# rev_b.net
KiCad netlist of a schematic drawn in EAGLE
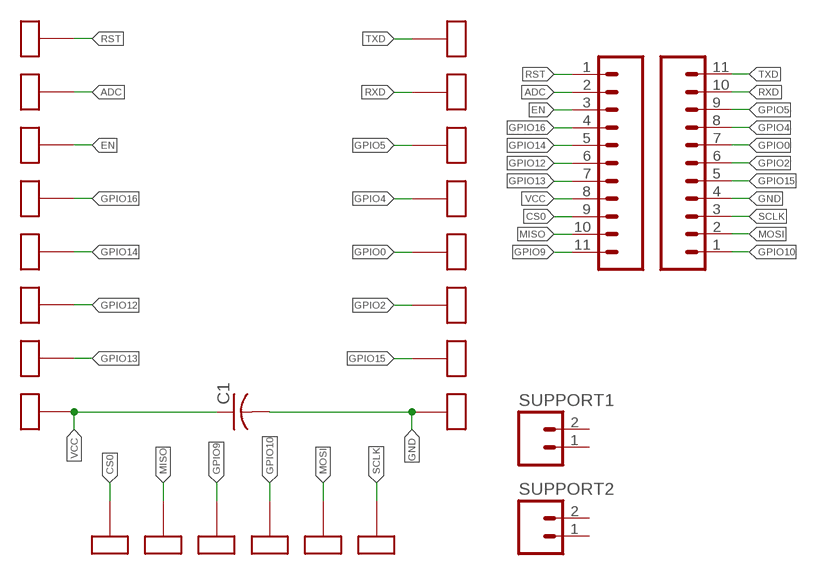
[diagram p0: schematic, sheet 1]

(export (version "E")
  (design (tool "Eeschema 10.0.6"))
  (components
    (comp (ref "C1")
      (value "C-USC0805")
      (footprint "eagle-import:C0805")
      (libsource (lib "eagle-import") (part "C-USC0805"))
    )
    (comp (ref "JP1")
      (value "M11LOCK")
      (footprint "eagle-import:1X11_LOCK")
      (libsource (lib "eagle-import") (part "M11LOCK"))
    )
    (comp (ref "JP2")
      (value "M11LOCK")
      (footprint "eagle-import:1X11_LOCK")
      (libsource (lib "eagle-import") (part "M11LOCK"))
    )
    (comp (ref "SUPPORT1")
      (value "M02LOCK")
      (footprint "eagle-import:1X02_LOCK")
      (libsource (lib "eagle-import") (part "M02LOCK"))
    )
    (comp (ref "SUPPORT2")
      (value "M02LOCK")
      (footprint "eagle-import:1X02_LOCK")
      (libsource (lib "eagle-import") (part "M02LOCK"))
    )
    (comp (ref "U$2")
      (value "1MMPOGO")
      (footprint "eagle-import:1MMPOGO")
      (libsource (lib "eagle-import") (part "1MMPOGO"))
    )
    (comp (ref "U$3")
      (value "1MMPOGO")
      (footprint "eagle-import:1MMPOGO")
      (libsource (lib "eagle-import") (part "1MMPOGO"))
    )
    (comp (ref "U$4")
      (value "1MMPOGO")
      (footprint "eagle-import:1MMPOGO")
      (libsource (lib "eagle-import") (part "1MMPOGO"))
    )
    (comp (ref "U$5")
      (value "1MMPOGO")
      (footprint "eagle-import:1MMPOGO")
      (libsource (lib "eagle-import") (part "1MMPOGO"))
    )
    (comp (ref "U$6")
      (value "1MMPOGO")
      (footprint "eagle-import:1MMPOGO")
      (libsource (lib "eagle-import") (part "1MMPOGO"))
    )
    (comp (ref "U$7")
      (value "1MMPOGO")
      (footprint "eagle-import:1MMPOGO")
      (libsource (lib "eagle-import") (part "1MMPOGO"))
    )
    (comp (ref "U$8")
      (value "1MMPOGO")
      (footprint "eagle-import:1MMPOGO")
      (libsource (lib "eagle-import") (part "1MMPOGO"))
    )
    (comp (ref "U$9")
      (value "1MMPOGO")
      (footprint "eagle-import:1MMPOGO")
      (libsource (lib "eagle-import") (part "1MMPOGO"))
    )
    (comp (ref "U$10")
      (value "1MMPOGO")
      (footprint "eagle-import:1MMPOGO")
      (libsource (lib "eagle-import") (part "1MMPOGO"))
    )
    (comp (ref "U$11")
      (value "1MMPOGO")
      (footprint "eagle-import:1MMPOGO")
      (libsource (lib "eagle-import") (part "1MMPOGO"))
    )
    (comp (ref "U$12")
      (value "1MMPOGO")
      (footprint "eagle-import:1MMPOGO")
      (libsource (lib "eagle-import") (part "1MMPOGO"))
    )
    (comp (ref "U$13")
      (value "1MMPOGO")
      (footprint "eagle-import:1MMPOGO")
      (libsource (lib "eagle-import") (part "1MMPOGO"))
    )
    (comp (ref "U$14")
      (value "1MMPOGO")
      (footprint "eagle-import:1MMPOGO")
      (libsource (lib "eagle-import") (part "1MMPOGO"))
    )
    (comp (ref "U$15")
      (value "1MMPOGO")
      (footprint "eagle-import:1MMPOGO")
      (libsource (lib "eagle-import") (part "1MMPOGO"))
    )
    (comp (ref "U$16")
      (value "1MMPOGO")
      (footprint "eagle-import:1MMPOGO")
      (libsource (lib "eagle-import") (part "1MMPOGO"))
    )
    (comp (ref "U$17")
      (value "1MMPOGO")
      (footprint "eagle-import:1MMPOGO")
      (libsource (lib "eagle-import") (part "1MMPOGO"))
    )
    (comp (ref "U$18")
      (value "1MMPOGO")
      (footprint "eagle-import:1MMPOGO")
      (libsource (lib "eagle-import") (part "1MMPOGO"))
    )
    (comp (ref "U$19")
      (value "1MMPOGO")
      (footprint "eagle-import:1MMPOGO")
      (libsource (lib "eagle-import") (part "1MMPOGO"))
    )
    (comp (ref "U$20")
      (value "1MMPOGO")
      (footprint "eagle-import:1MMPOGO")
      (libsource (lib "eagle-import") (part "1MMPOGO"))
    )
    (comp (ref "U$21")
      (value "1MMPOGO")
      (footprint "eagle-import:1MMPOGO")
      (libsource (lib "eagle-import") (part "1MMPOGO"))
    )
    (comp (ref "U$22")
      (value "1MMPOGO")
      (footprint "eagle-import:1MMPOGO")
      (libsource (lib "eagle-import") (part "1MMPOGO"))
    )
    (comp (ref "U$23")
      (value "1MMPOGO")
      (footprint "eagle-import:1MMPOGO")
      (libsource (lib "eagle-import") (part "1MMPOGO"))
    )
  )
  (nets
    (net (code "1") (name "ADC") (class "Default")
      (node (ref "JP1") (pin "2") (pinfunction "2_2") (pintype "passive"))
      (node (ref "U$3") (pin "POGO") (pinfunction "P_POGO") (pintype "bidirectional"))
    )
    (net (code "2") (name "CS0") (class "Default")
      (node (ref "JP1") (pin "9") (pinfunction "9_9") (pintype "passive"))
      (node (ref "U$10") (pin "POGO") (pinfunction "P_POGO") (pintype "bidirectional"))
    )
    (net (code "3") (name "EN") (class "Default")
      (node (ref "JP1") (pin "3") (pinfunction "3_3") (pintype "passive"))
      (node (ref "U$4") (pin "POGO") (pinfunction "P_POGO") (pintype "bidirectional"))
    )
    (net (code "4") (name "GND") (class "Default")
      (node (ref "C1") (pin "2") (pinfunction "2_2") (pintype "passive"))
      (node (ref "JP2") (pin "4") (pinfunction "4_4") (pintype "passive"))
      (node (ref "U$16") (pin "POGO") (pinfunction "P_POGO") (pintype "bidirectional"))
    )
    (net (code "5") (name "GPIO0") (class "Default")
      (node (ref "JP2") (pin "7") (pinfunction "7_7") (pintype "passive"))
      (node (ref "U$19") (pin "POGO") (pinfunction "P_POGO") (pintype "bidirectional"))
    )
    (net (code "6") (name "GPIO2") (class "Default")
      (node (ref "JP2") (pin "6") (pinfunction "6_6") (pintype "passive"))
      (node (ref "U$18") (pin "POGO") (pinfunction "P_POGO") (pintype "bidirectional"))
    )
    (net (code "7") (name "GPIO4") (class "Default")
      (node (ref "JP2") (pin "8") (pinfunction "8_8") (pintype "passive"))
      (node (ref "U$20") (pin "POGO") (pinfunction "P_POGO") (pintype "bidirectional"))
    )
    (net (code "8") (name "GPIO5") (class "Default")
      (node (ref "JP2") (pin "9") (pinfunction "9_9") (pintype "passive"))
      (node (ref "U$21") (pin "POGO") (pinfunction "P_POGO") (pintype "bidirectional"))
    )
    (net (code "9") (name "GPIO9") (class "Default")
      (node (ref "JP1") (pin "11") (pinfunction "11_11") (pintype "passive"))
      (node (ref "U$12") (pin "POGO") (pinfunction "P_POGO") (pintype "bidirectional"))
    )
    (net (code "10") (name "GPIO10") (class "Default")
      (node (ref "JP2") (pin "1") (pinfunction "1_1") (pintype "passive"))
      (node (ref "U$13") (pin "POGO") (pinfunction "P_POGO") (pintype "bidirectional"))
    )
    (net (code "11") (name "GPIO12") (class "Default")
      (node (ref "JP1") (pin "6") (pinfunction "6_6") (pintype "passive"))
      (node (ref "U$7") (pin "POGO") (pinfunction "P_POGO") (pintype "bidirectional"))
    )
    (net (code "12") (name "GPIO13") (class "Default")
      (node (ref "JP1") (pin "7") (pinfunction "7_7") (pintype "passive"))
      (node (ref "U$8") (pin "POGO") (pinfunction "P_POGO") (pintype "bidirectional"))
    )
    (net (code "13") (name "GPIO14") (class "Default")
      (node (ref "JP1") (pin "5") (pinfunction "5_5") (pintype "passive"))
      (node (ref "U$6") (pin "POGO") (pinfunction "P_POGO") (pintype "bidirectional"))
    )
    (net (code "14") (name "GPIO15") (class "Default")
      (node (ref "JP2") (pin "5") (pinfunction "5_5") (pintype "passive"))
      (node (ref "U$17") (pin "POGO") (pinfunction "P_POGO") (pintype "bidirectional"))
    )
    (net (code "15") (name "GPIO16") (class "Default")
      (node (ref "JP1") (pin "4") (pinfunction "4_4") (pintype "passive"))
      (node (ref "U$5") (pin "POGO") (pinfunction "P_POGO") (pintype "bidirectional"))
    )
    (net (code "16") (name "MISO") (class "Default")
      (node (ref "JP1") (pin "10") (pinfunction "10_10") (pintype "passive"))
      (node (ref "U$11") (pin "POGO") (pinfunction "P_POGO") (pintype "bidirectional"))
    )
    (net (code "17") (name "MOSI") (class "Default")
      (node (ref "JP2") (pin "2") (pinfunction "2_2") (pintype "passive"))
      (node (ref "U$14") (pin "POGO") (pinfunction "P_POGO") (pintype "bidirectional"))
    )
    (net (code "18") (name "RST") (class "Default")
      (node (ref "JP1") (pin "1") (pinfunction "1_1") (pintype "passive"))
      (node (ref "U$2") (pin "POGO") (pinfunction "P_POGO") (pintype "bidirectional"))
    )
    (net (code "19") (name "RXD") (class "Default")
      (node (ref "JP2") (pin "10") (pinfunction "10_10") (pintype "passive"))
      (node (ref "U$22") (pin "POGO") (pinfunction "P_POGO") (pintype "bidirectional"))
    )
    (net (code "20") (name "SCLK") (class "Default")
      (node (ref "JP2") (pin "3") (pinfunction "3_3") (pintype "passive"))
      (node (ref "U$15") (pin "POGO") (pinfunction "P_POGO") (pintype "bidirectional"))
    )
    (net (code "21") (name "TXD") (class "Default")
      (node (ref "JP2") (pin "11") (pinfunction "11_11") (pintype "passive"))
      (node (ref "U$23") (pin "POGO") (pinfunction "P_POGO") (pintype "bidirectional"))
    )
    (net (code "22") (name "VCC") (class "Default")
      (node (ref "C1") (pin "1") (pinfunction "1_1") (pintype "passive"))
      (node (ref "JP1") (pin "8") (pinfunction "8_8") (pintype "passive"))
      (node (ref "U$9") (pin "POGO") (pinfunction "P_POGO") (pintype "bidirectional"))
    )
    (net (code "23") (name "unconnected-(SUPPORT1-Pad1)") (class "Default")
      (node (ref "SUPPORT1") (pin "1") (pinfunction "1_1") (pintype "passive"))
    )
    (net (code "24") (name "unconnected-(SUPPORT1-Pad2)") (class "Default")
      (node (ref "SUPPORT1") (pin "2") (pinfunction "2_2") (pintype "passive"))
    )
    (net (code "25") (name "unconnected-(SUPPORT2-Pad1)") (class "Default")
      (node (ref "SUPPORT2") (pin "1") (pinfunction "1_1") (pintype "passive"))
    )
    (net (code "26") (name "unconnected-(SUPPORT2-Pad2)") (class "Default")
      (node (ref "SUPPORT2") (pin "2") (pinfunction "2_2") (pintype "passive"))
    )
  )
)
